# PowerSupply.net
KiCad netlist of a schematic drawn in Altium Designer
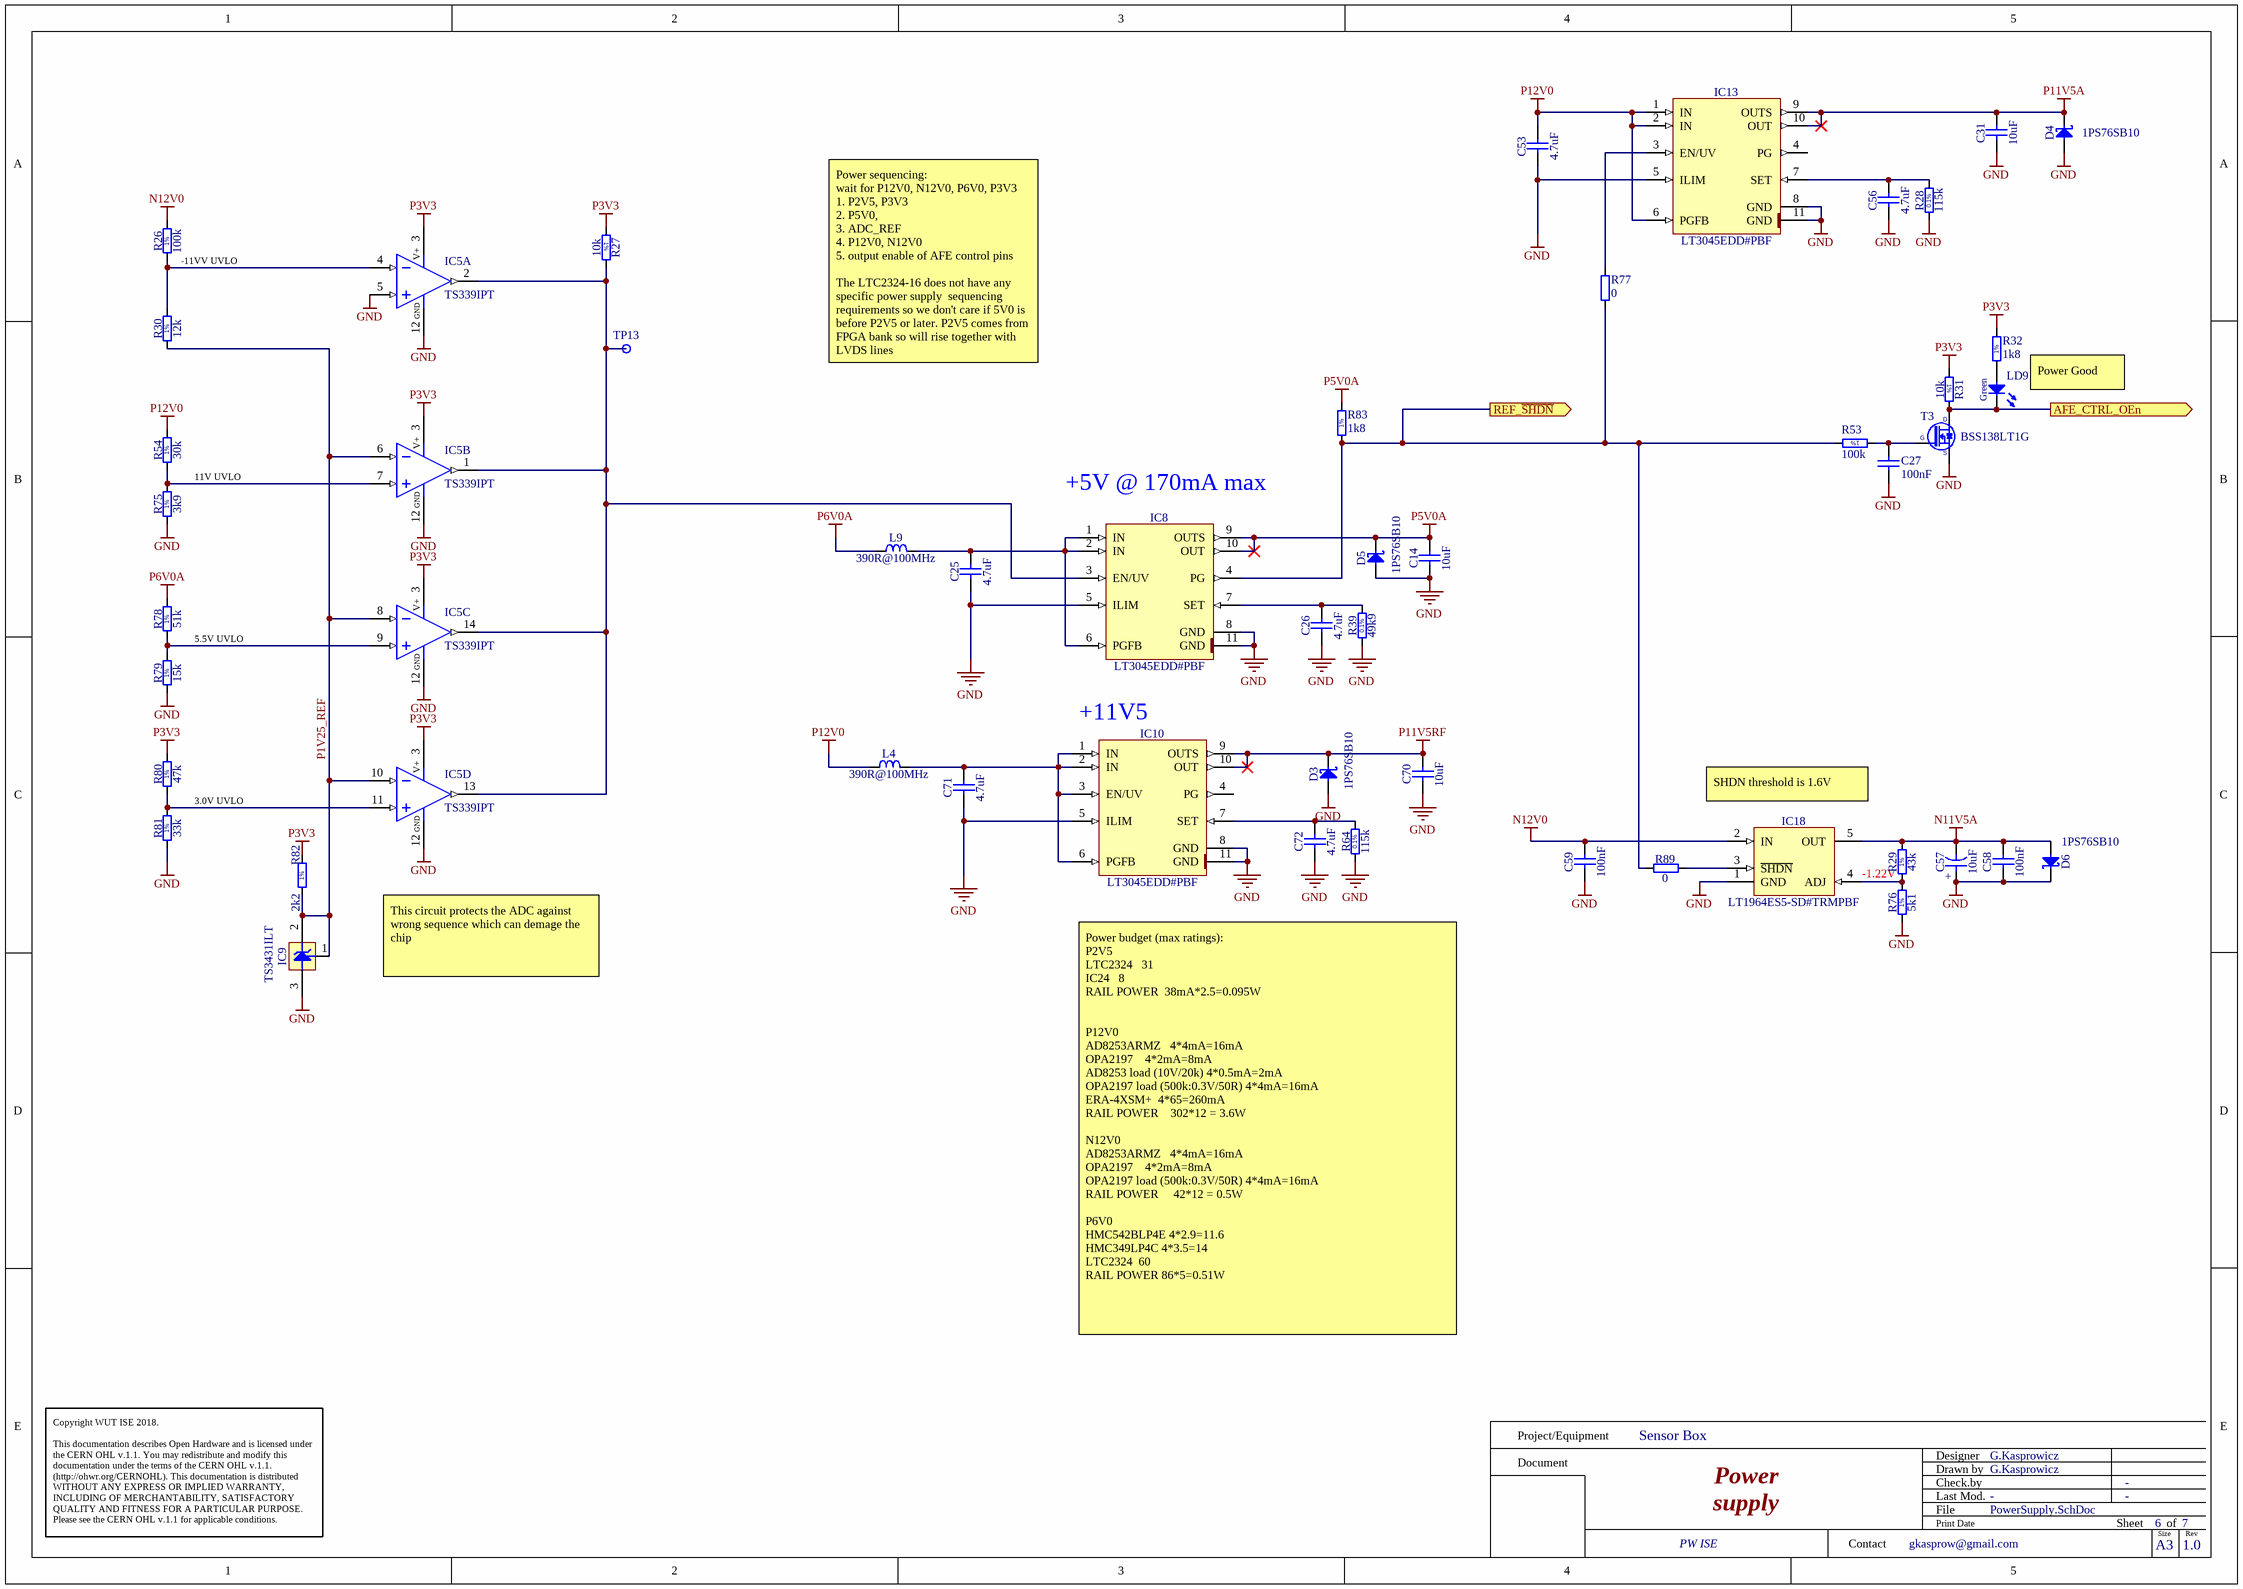
[diagram p0: PowerSupply.SchDoc]

(export (version "E")
  (design (tool "Eeschema 10.0.6"))
  (components
    (comp (ref "C14")
      (value "10uF")
      (footprint "CAPC1608X87N")
      (description "Non-polarised capacitor")
      (fields
        (field (name "PART NUMBER") "CC0603_10UF_6.3V_20%_X5R")
        (field (name "VOLTAGE") "6.3V")
        (field (name "AUTHOR") "CERN DEM JLC")
      )
      (libsource (lib "Capacitors") (part "Capacitor - non polarized"))
    )
    (comp (ref "C25")
      (value "4.7uF")
      (footprint "CAPC1709X95N")
      (description "Non-polarised capacitor")
      (fields
        (field (name "PART NUMBER") "CC0603_4.7UF_16V_10%_X5R")
        (field (name "VOLTAGE") "16V")
        (field (name "AUTHOR") "CERN DEM JLC")
      )
      (libsource (lib "Capacitors") (part "Capacitor - non polarized"))
    )
    (comp (ref "C26")
      (value "4.7uF")
      (footprint "CAPC1709X95N")
      (description "Non-polarised capacitor")
      (fields
        (field (name "PART NUMBER") "CC0603_4.7UF_16V_10%_X5R")
        (field (name "VOLTAGE") "16V")
        (field (name "AUTHOR") "CERN DEM JLC")
      )
      (libsource (lib "Capacitors") (part "Capacitor - non polarized"))
    )
    (comp (ref "C27")
      (value "100nF")
      (footprint "CAPC1005X55N")
      (description "Non-polarised capacitor")
      (fields
        (field (name "PART NUMBER") "CC0402_100NF_16V_10%_X5R")
        (field (name "VOLTAGE") "16V")
        (field (name "AUTHOR") "CERN DEM JLC")
      )
      (libsource (lib "Capacitors") (part "Capacitor - non polarized"))
    )
    (comp (ref "C31")
      (value "10uF")
      (footprint "CAPC1608X87N")
      (description "Non-polarised capacitor")
      (fields
        (field (name "PART NUMBER") "CC0603_10UF_6.3V_20%_X5R")
        (field (name "VOLTAGE") "6.3V")
        (field (name "AUTHOR") "CERN DEM JLC")
      )
      (libsource (lib "Capacitors") (part "Capacitor - non polarized"))
    )
    (comp (ref "C53")
      (value "4.7uF")
      (footprint "CAPC1709X95N")
      (description "Non-polarised capacitor")
      (fields
        (field (name "PART NUMBER") "CC0603_4.7UF_16V_10%_X5R")
        (field (name "VOLTAGE") "16V")
        (field (name "AUTHOR") "CERN DEM JLC")
      )
      (libsource (lib "Capacitors") (part "Capacitor - non polarized"))
    )
    (comp (ref "C56")
      (value "4.7uF")
      (footprint "CAPC1709X95N")
      (description "Non-polarised capacitor")
      (fields
        (field (name "PART NUMBER") "CC0603_4.7UF_16V_10%_X5R")
        (field (name "VOLTAGE") "16V")
        (field (name "AUTHOR") "CERN DEM JLC")
      )
      (libsource (lib "Capacitors") (part "Capacitor - non polarized"))
    )
    (comp (ref "C57")
      (value "10uF")
      (footprint "CAPMP3216X180N")
      (description "Polarised capacitor")
      (fields
        (field (name "PART NUMBER") "CTE3216-18_10UF_16V_20%_AVX_TCJ")
        (field (name "VOLTAGE") "16V")
        (field (name "AUTHOR") "CERN DEM JLC")
      )
      (libsource (lib "Capacitors") (part "Capacitor - polarized"))
    )
    (comp (ref "C58")
      (value "100nF")
      (footprint "CAPC1005X55N")
      (description "Non-polarised capacitor")
      (fields
        (field (name "PART NUMBER") "CC0402_100NF_16V_10%_X5R")
        (field (name "VOLTAGE") "16V")
        (field (name "AUTHOR") "CERN DEM JLC")
      )
      (libsource (lib "Capacitors") (part "Capacitor - non polarized"))
    )
    (comp (ref "C59")
      (value "100nF")
      (footprint "CAPC1005X55N")
      (description "Non-polarised capacitor")
      (fields
        (field (name "PART NUMBER") "CC0402_100NF_16V_10%_X5R")
        (field (name "VOLTAGE") "16V")
        (field (name "AUTHOR") "CERN DEM JLC")
      )
      (libsource (lib "Capacitors") (part "Capacitor - non polarized"))
    )
    (comp (ref "C70")
      (value "10uF")
      (footprint "CAPC1608X87N")
      (description "Non-polarised capacitor")
      (fields
        (field (name "PART NUMBER") "CC0603_10UF_6.3V_20%_X5R")
        (field (name "VOLTAGE") "6.3V")
        (field (name "AUTHOR") "CERN DEM JLC")
      )
      (libsource (lib "Capacitors") (part "Capacitor - non polarized"))
    )
    (comp (ref "C71")
      (value "4.7uF")
      (footprint "CAPC1709X95N")
      (description "Non-polarised capacitor")
      (fields
        (field (name "PART NUMBER") "CC0603_4.7UF_16V_10%_X5R")
        (field (name "VOLTAGE") "16V")
        (field (name "AUTHOR") "CERN DEM JLC")
      )
      (libsource (lib "Capacitors") (part "Capacitor - non polarized"))
    )
    (comp (ref "C72")
      (value "4.7uF")
      (footprint "CAPC1709X95N")
      (description "Non-polarised capacitor")
      (fields
        (field (name "PART NUMBER") "CC0603_4.7UF_16V_10%_X5R")
        (field (name "VOLTAGE") "16V")
        (field (name "AUTHOR") "CERN DEM JLC")
      )
      (libsource (lib "Capacitors") (part "Capacitor - non polarized"))
    )
    (comp (ref "D3")
      (value "1PS76SB10")
      (footprint "SOD2512X110N")
      (description "Schottky Diode")
      (fields
        (field (name "VOLTAGE") "30V")
        (field (name "POWER") "200mA")
        (field (name "AUTHOR") "CERN DEM JLC")
      )
      (libsource (lib "ICs And Semiconductors") (part "Diode Schottky"))
    )
    (comp (ref "D4")
      (value "1PS76SB10")
      (footprint "SOD2512X110N")
      (description "Schottky Diode")
      (fields
        (field (name "VOLTAGE") "30V")
        (field (name "POWER") "200mA")
        (field (name "AUTHOR") "CERN DEM JLC")
      )
      (libsource (lib "ICs And Semiconductors") (part "Diode Schottky"))
    )
    (comp (ref "D5")
      (value "1PS76SB10")
      (footprint "SOD2512X110N")
      (description "Schottky Diode")
      (fields
        (field (name "VOLTAGE") "30V")
        (field (name "POWER") "200mA")
        (field (name "AUTHOR") "CERN DEM JLC")
      )
      (libsource (lib "ICs And Semiconductors") (part "Diode Schottky"))
    )
    (comp (ref "D6")
      (value "1PS76SB10")
      (footprint "SOD2512X110N")
      (description "Schottky Diode")
      (fields
        (field (name "VOLTAGE") "30V")
        (field (name "POWER") "200mA")
        (field (name "AUTHOR") "CERN DEM JLC")
      )
      (libsource (lib "ICs And Semiconductors") (part "Diode Schottky"))
    )
    (comp (ref "IC5")
      (value "TS339IPT")
      (footprint "SOP65P640X120-14N")
      (description "Quad comparator")
      (fields (field (name "MANUFACTURER") "ST") (field (name "AUTHOR") "GK"))
      (libsource (lib "LIBRARY_SCH") (part "CMP_TS339"))
    )
    (comp (ref "IC8")
      (value "LT3045EDD#PBF")
      (footprint "SON50P300X300X80-11N-R175X248")
      (description "20V, 500mA, Ultralow Noise, Ultrahigh PSRR Linear Regulator")
      (fields (field (name "MANUFACTURER") "LINEAR TECHNOLOGY") (field (name "AUTHOR") "CERN DEM JLC"))
      (libsource (lib "ICs And Semiconductors") (part "LT3045EDD"))
    )
    (comp (ref "IC9")
      (value "TS3431ILT")
      (footprint "SOT95P237X112-3N")
      (description "Precision Reference 1=Adj 2=Cathode 3=Anode")
      (fields (field (name "MANUFACTURER") "ST MICROELECTRONICS") (field (name "AUTHOR") "CERN DEM JLC"))
      (libsource (lib "ICs And Semiconductors") (part "VREF 1ADJ-2C-3A"))
    )
    (comp (ref "IC10")
      (value "LT3045EDD#PBF")
      (footprint "SON50P300X300X80-11N-R175X248")
      (description "20V, 500mA, Ultralow Noise, Ultrahigh PSRR Linear Regulator")
      (fields (field (name "MANUFACTURER") "LINEAR TECHNOLOGY") (field (name "AUTHOR") "CERN DEM JLC"))
      (libsource (lib "ICs And Semiconductors") (part "LT3045EDD"))
    )
    (comp (ref "IC13")
      (value "LT3045EDD#PBF")
      (footprint "SON50P300X300X80-11N-R175X248")
      (description "20V, 500mA, Ultralow Noise, Ultrahigh PSRR Linear Regulator")
      (fields (field (name "MANUFACTURER") "LINEAR TECHNOLOGY") (field (name "AUTHOR") "CERN DEM JLC"))
      (libsource (lib "ICs And Semiconductors") (part "LT3045EDD"))
    )
    (comp (ref "IC18")
      (value "LT1964ES5-SD#TRMPBF")
      (footprint "SOT95P280X100-5N")
      (description "200mA, Low Noise, Low Dropout Negative Micropower Regulator")
      (fields (field (name "MANUFACTURER") "LINEAR TECHNOLOGY") (field (name "AUTHOR") "CERN DEM JLC"))
      (libsource (lib "ICs And Semiconductors") (part "LT1964-SD"))
    )
    (comp (ref "L4")
      (value "390R@100MHz")
      (footprint "INDC1608X95N")
      (description "Inductor")
      (fields
        (field (name "PART NUMBER") "IND0603_TDK_MPZ1608R391A")
        (field (name "POWER") "1.2A")
        (field (name "AUTHOR") "CERN DEM JLC")
      )
      (libsource (lib "Inductors & Transformers") (part "Inductor"))
    )
    (comp (ref "L9")
      (value "390R@100MHz")
      (footprint "INDC1608X95N")
      (description "Inductor")
      (fields
        (field (name "PART NUMBER") "IND0603_TDK_MPZ1608R391A")
        (field (name "POWER") "1.2A")
        (field (name "AUTHOR") "CERN DEM JLC")
      )
      (libsource (lib "Inductors & Transformers") (part "Inductor"))
    )
    (comp (ref "LD9")
      (value "Green")
      (footprint "LED_KINGBRIGHT_KPH-1608CGCK")
      (description "LED Green 1C 2A")
      (fields
        (field (name "PART NUMBER") "LED_KINGBRIGHT_KPH-1608CGCK")
        (field (name "MANUFACTURER") "KINGBRIGHT")
        (field (name "AUTHOR") "CERN DEM JLC")
      )
      (libsource (lib "ICs And Semiconductors") (part "LED Green 1C 2A"))
    )
    (comp (ref "R26")
      (value "100k")
      (footprint "RESC1005X40N")
      (description "Resistor - 1%")
      (fields
        (field (name "PART NUMBER") "R0402_100K_1%_0.0625W_100PPM")
        (field (name "POWER") "0.0625W")
        (field (name "AUTHOR") "CERN DEM JLC")
      )
      (libsource (lib "Resistors") (part "Resistor - 1%"))
    )
    (comp (ref "R27")
      (value "10k")
      (footprint "RESC1005X40N")
      (description "Resistor - 1%")
      (fields
        (field (name "PART NUMBER") "R0402_10K_1%_0.0625W_100PPM")
        (field (name "POWER") "0.0625W")
        (field (name "AUTHOR") "CERN DEM JLC")
      )
      (libsource (lib "Resistors") (part "Resistor - 1%"))
    )
    (comp (ref "R28")
      (value "115k")
      (footprint "RESC1608X55N")
      (description "Resistor - 0.1%")
      (fields
        (field (name "PART NUMBER") "R0603_115K_0.1%_0.063W_10PPM")
        (field (name "POWER") "0.063W")
        (field (name "AUTHOR") "CERN DEM JLC")
      )
      (libsource (lib "Resistors") (part "Resistor - 0.1%"))
    )
    (comp (ref "R29")
      (value "43k")
      (footprint "RESC1005X40N")
      (description "Resistor - 1%")
      (fields
        (field (name "PART NUMBER") "R0402_43K_1%_0.0625W_100PPM")
        (field (name "POWER") "0.0625W")
        (field (name "AUTHOR") "CERN DEM JLC")
      )
      (libsource (lib "Resistors") (part "Resistor - 1%"))
    )
    (comp (ref "R30")
      (value "12k")
      (footprint "RESC1005X40N")
      (description "Resistor - 1%")
      (fields
        (field (name "PART NUMBER") "R0402_12K_1%_0.0625W_100PPM")
        (field (name "POWER") "0.0625W")
        (field (name "AUTHOR") "CERN DEM JLC")
      )
      (libsource (lib "Resistors") (part "Resistor - 1%"))
    )
    (comp (ref "R31")
      (value "10k")
      (footprint "RESC1005X40N")
      (description "Resistor - 1%")
      (fields
        (field (name "PART NUMBER") "R0402_10K_1%_0.0625W_100PPM")
        (field (name "POWER") "0.0625W")
        (field (name "AUTHOR") "CERN DEM JLC")
      )
      (libsource (lib "Resistors") (part "Resistor - 1%"))
    )
    (comp (ref "R32")
      (value "1k8")
      (footprint "RESC1608X55N")
      (description "Resistor - 1%")
      (fields
        (field (name "PART NUMBER") "R0603_1K8_1%_0.1W_100PPM")
        (field (name "POWER") "0.1W")
        (field (name "AUTHOR") "CERN DEM JLC")
      )
      (libsource (lib "Resistors") (part "Resistor - 1%"))
    )
    (comp (ref "R39")
      (value "49k9")
      (footprint "RESC1608X55N")
      (description "Resistor - 0.1%")
      (fields
        (field (name "PART NUMBER") "R0603_49K9_0.1%_0.063W_10PPM")
        (field (name "POWER") "0.063W")
        (field (name "AUTHOR") "CERN DEM JLC")
      )
      (libsource (lib "Resistors") (part "Resistor - 0.1%"))
    )
    (comp (ref "R53")
      (value "100k")
      (footprint "RESC1608X55N")
      (description "Resistor - 1%")
      (fields
        (field (name "PART NUMBER") "R0603_100K_1%_0.1W_100PPM")
        (field (name "POWER") "0.1W")
        (field (name "AUTHOR") "CERN DEM JLC")
      )
      (libsource (lib "Resistors") (part "Resistor - 1%"))
    )
    (comp (ref "R54")
      (value "30k")
      (footprint "RESC1005X40N")
      (description "Resistor - 1%")
      (fields
        (field (name "PART NUMBER") "R0402_30K_1%_0.0625W_100PPM")
        (field (name "POWER") "0.0625W")
        (field (name "AUTHOR") "CERN DEM JLC")
      )
      (libsource (lib "Resistors") (part "Resistor - 1%"))
    )
    (comp (ref "R64")
      (value "115k")
      (footprint "RESC1608X55N")
      (description "Resistor - 0.1%")
      (fields
        (field (name "PART NUMBER") "R0603_115K_0.1%_0.063W_10PPM")
        (field (name "POWER") "0.063W")
        (field (name "AUTHOR") "CERN DEM JLC")
      )
      (libsource (lib "Resistors") (part "Resistor - 0.1%"))
    )
    (comp (ref "R75")
      (value "3k9")
      (footprint "RESC1005X40N")
      (description "Resistor - 1%")
      (fields
        (field (name "PART NUMBER") "R0402_3K9_1%_0.0625W_100PPM")
        (field (name "POWER") "0.0625W")
        (field (name "AUTHOR") "CERN DEM JLC")
      )
      (libsource (lib "Resistors") (part "Resistor - 1%"))
    )
    (comp (ref "R76")
      (value "5k1")
      (footprint "RESC1005X40N")
      (description "Resistor - 1%")
      (fields
        (field (name "PART NUMBER") "R0402_5K1_1%_0.0625W_100PPM")
        (field (name "POWER") "0.0625W")
        (field (name "AUTHOR") "CERN DEM JLC")
      )
      (libsource (lib "Resistors") (part "Resistor - 1%"))
    )
    (comp (ref "R77")
      (value "0")
      (footprint "RESC1005X40N")
      (description "Resistor")
      (fields
        (field (name "PART NUMBER") "R0402_0R_JUMPER")
        (field (name "MANUFACTURER") "GENERIC")
        (field (name "AUTHOR") "CERN DEM JLC")
      )
      (libsource (lib "Resistors") (part "Resistor"))
    )
    (comp (ref "R78")
      (value "51k")
      (footprint "RESC1005X40N")
      (description "Resistor - 1%")
      (fields
        (field (name "PART NUMBER") "R0402_51K_1%_0.0625W_100PPM")
        (field (name "POWER") "0.0625W")
        (field (name "AUTHOR") "CERN DEM JLC")
      )
      (libsource (lib "Resistors") (part "Resistor - 1%"))
    )
    (comp (ref "R79")
      (value "15k")
      (footprint "RESC1005X40N")
      (description "Resistor - 1%")
      (fields
        (field (name "PART NUMBER") "R0402_15K_1%_0.0625W_100PPM")
        (field (name "POWER") "0.0625W")
        (field (name "AUTHOR") "CERN DEM JMW")
      )
      (libsource (lib "Resistors") (part "Resistor - 1%"))
    )
    (comp (ref "R80")
      (value "47k")
      (footprint "RESC1005X40N")
      (description "Resistor - 1%")
      (fields
        (field (name "PART NUMBER") "R0402_47K_1%_0.0625W_100PPM")
        (field (name "POWER") "0.0625W")
        (field (name "AUTHOR") "CERN DEM JLC")
      )
      (libsource (lib "Resistors") (part "Resistor - 1%"))
    )
    (comp (ref "R81")
      (value "33k")
      (footprint "RESC1005X40N")
      (description "Resistor - 1%")
      (fields
        (field (name "PART NUMBER") "R0402_33K_1%_0.0625W_100PPM")
        (field (name "POWER") "0.0625W")
        (field (name "AUTHOR") "CERN DEM JLC")
      )
      (libsource (lib "Resistors") (part "Resistor - 1%"))
    )
    (comp (ref "R82")
      (value "2k2")
      (footprint "RESC1005X40N")
      (description "Resistor - 1%")
      (fields
        (field (name "PART NUMBER") "R0402_2K2_1%_0.0625W_100PPM")
        (field (name "POWER") "0.0625W")
        (field (name "AUTHOR") "CERN DEM JLC")
      )
      (libsource (lib "Resistors") (part "Resistor - 1%"))
    )
    (comp (ref "R83")
      (value "1k8")
      (footprint "RESC1608X55N")
      (description "Resistor - 1%")
      (fields
        (field (name "PART NUMBER") "R0603_1K8_1%_0.1W_100PPM")
        (field (name "POWER") "0.1W")
        (field (name "AUTHOR") "CERN DEM JLC")
      )
      (libsource (lib "Resistors") (part "Resistor - 1%"))
    )
    (comp (ref "R89")
      (value "0")
      (footprint "RESC1005X40N")
      (description "Resistor")
      (fields
        (field (name "PART NUMBER") "R0402_0R_JUMPER")
        (field (name "MANUFACTURER") "GENERIC")
        (field (name "AUTHOR") "CERN DEM JLC")
      )
      (libsource (lib "Resistors") (part "Resistor"))
    )
    (comp (ref "T3")
      (value "BSS138LT1G")
      (footprint "SOT95P240X110-3N")
      (description "N-CHANNEL MOSFET WITH DIODE")
      (fields (field (name "MANUFACTURER") "ON SEMICONDUCTOR") (field (name "AUTHOR") "CERN DEM JLC"))
      (libsource (lib "ICs And Semiconductors") (part "N-MOSFET-D 1G 2S 3D"))
    )
    (comp (ref "TP13")
      (value "Test Point")
      (footprint "TPS127")
      (fields (field (name "PART NUMBER") "SMD_PAD_1.27X1.27MM") (field (name "AUTHOR") "CERN DEM JLC"))
      (libsource (lib "Eletro-mechanical") (part "Test Point"))
    )
  )
  (nets
    (net (code "1") (name "/AFE_CTRL_OEn") (class "Default")
      (node (ref "LD9") (pin "1") (pinfunction "C_1") (pintype "passive"))
      (node (ref "R31") (pin "2") (pinfunction "2_2") (pintype "passive"))
      (node (ref "T3") (pin "3") (pinfunction "D_3") (pintype "passive"))
    )
    (net (code "2") (name "/P1V25_REF") (class "Default")
      (node (ref "IC5") (pin "10") (pinfunction "IN-_10") (pintype "input"))
      (node (ref "IC5") (pin "6") (pinfunction "IN-_6") (pintype "input"))
      (node (ref "IC5") (pin "8") (pinfunction "IN-_8") (pintype "input"))
      (node (ref "IC9") (pin "1") (pinfunction "Adj_1") (pintype "passive"))
      (node (ref "IC9") (pin "2") (pinfunction "C_2") (pintype "passive"))
      (node (ref "R30") (pin "1") (pinfunction "1_1") (pintype "passive"))
      (node (ref "R82") (pin "1") (pinfunction "1_1") (pintype "passive"))
    )
    (net (code "3") (name "/REF_~{SHDN}") (class "Default")
      (node (ref "IC8") (pin "4") (pinfunction "PG_4") (pintype "output"))
      (node (ref "R53") (pin "2") (pinfunction "2_2") (pintype "passive"))
      (node (ref "R77") (pin "1") (pinfunction "1_1") (pintype "passive"))
      (node (ref "R83") (pin "1") (pinfunction "1_1") (pintype "passive"))
      (node (ref "R89") (pin "1") (pinfunction "1_1") (pintype "passive"))
    )
    (net (code "4") (name "GND") (class "Default")
      (node (ref "C14") (pin "1") (pinfunction "1_1") (pintype "passive"))
      (node (ref "C25") (pin "1") (pinfunction "1_1") (pintype "passive"))
      (node (ref "C26") (pin "1") (pinfunction "1_1") (pintype "passive"))
      (node (ref "C27") (pin "2") (pinfunction "2_2") (pintype "passive"))
      (node (ref "C31") (pin "1") (pinfunction "1_1") (pintype "passive"))
      (node (ref "C53") (pin "1") (pinfunction "1_1") (pintype "passive"))
      (node (ref "C56") (pin "1") (pinfunction "1_1") (pintype "passive"))
      (node (ref "C57") (pin "1") (pinfunction "1_1") (pintype "passive"))
      (node (ref "C58") (pin "1") (pinfunction "1_1") (pintype "passive"))
      (node (ref "C59") (pin "1") (pinfunction "1_1") (pintype "passive"))
      (node (ref "C70") (pin "1") (pinfunction "1_1") (pintype "passive"))
      (node (ref "C71") (pin "1") (pinfunction "1_1") (pintype "passive"))
      (node (ref "C72") (pin "1") (pinfunction "1_1") (pintype "passive"))
      (node (ref "D3") (pin "2") (pinfunction "A_2") (pintype "passive"))
      (node (ref "D4") (pin "2") (pinfunction "A_2") (pintype "passive"))
      (node (ref "D5") (pin "2") (pinfunction "A_2") (pintype "passive"))
      (node (ref "D6") (pin "1") (pinfunction "C_1") (pintype "passive"))
      (node (ref "IC10") (pin "11") (pinfunction "GND_11") (pintype "power_in"))
      (node (ref "IC10") (pin "5") (pinfunction "ILIM_5") (pintype "input"))
      (node (ref "IC10") (pin "8") (pinfunction "GND_8") (pintype "power_in"))
      (node (ref "IC13") (pin "11") (pinfunction "GND_11") (pintype "power_in"))
      (node (ref "IC13") (pin "5") (pinfunction "ILIM_5") (pintype "input"))
      (node (ref "IC13") (pin "8") (pinfunction "GND_8") (pintype "power_in"))
      (node (ref "IC18") (pin "1") (pinfunction "GND_1") (pintype "power_in"))
      (node (ref "IC5") (pin "12") (pinfunction "GND_12") (pintype "power_in"))
      (node (ref "IC5") (pin "5") (pinfunction "IN+_5") (pintype "input"))
      (node (ref "IC8") (pin "11") (pinfunction "GND_11") (pintype "power_in"))
      (node (ref "IC8") (pin "5") (pinfunction "ILIM_5") (pintype "input"))
      (node (ref "IC8") (pin "8") (pinfunction "GND_8") (pintype "power_in"))
      (node (ref "IC9") (pin "3") (pinfunction "A_3") (pintype "passive"))
      (node (ref "R28") (pin "1") (pinfunction "1_1") (pintype "passive"))
      (node (ref "R39") (pin "1") (pinfunction "1_1") (pintype "passive"))
      (node (ref "R64") (pin "1") (pinfunction "1_1") (pintype "passive"))
      (node (ref "R75") (pin "1") (pinfunction "1_1") (pintype "passive"))
      (node (ref "R76") (pin "1") (pinfunction "1_1") (pintype "passive"))
      (node (ref "R79") (pin "1") (pinfunction "1_1") (pintype "passive"))
      (node (ref "R81") (pin "1") (pinfunction "1_1") (pintype "passive"))
      (node (ref "T3") (pin "2") (pinfunction "S_2") (pintype "passive"))
    )
    (net (code "5") (name "N11V5A") (class "Default")
      (node (ref "C57") (pin "2") (pinfunction "2_2") (pintype "passive"))
      (node (ref "C58") (pin "2") (pinfunction "2_2") (pintype "passive"))
      (node (ref "D6") (pin "2") (pinfunction "A_2") (pintype "passive"))
      (node (ref "IC18") (pin "5") (pinfunction "OUT_5") (pintype "power_in"))
      (node (ref "R29") (pin "2") (pinfunction "2_2") (pintype "passive"))
    )
    (net (code "6") (name "N12V0") (class "Default")
      (node (ref "C59") (pin "2") (pinfunction "2_2") (pintype "passive"))
      (node (ref "IC18") (pin "2") (pinfunction "IN_2") (pintype "input"))
      (node (ref "R26") (pin "2") (pinfunction "2_2") (pintype "passive"))
    )
    (net (code "7") (name "Net-(IC5A-IN-)") (class "Default")
      (node (ref "IC5") (pin "4") (pinfunction "IN-_4") (pintype "input"))
      (node (ref "R26") (pin "1") (pinfunction "1_1") (pintype "passive"))
      (node (ref "R30") (pin "2") (pinfunction "2_2") (pintype "passive"))
    )
    (net (code "8") (name "Net-(IC5A-OUT)") (class "Default")
      (node (ref "IC5") (pin "1") (pinfunction "OUT_1") (pintype "output"))
      (node (ref "IC5") (pin "13") (pinfunction "OUT_13") (pintype "output"))
      (node (ref "IC5") (pin "14") (pinfunction "OUT_14") (pintype "output"))
      (node (ref "IC5") (pin "2") (pinfunction "OUT_2") (pintype "output"))
      (node (ref "IC8") (pin "3") (pinfunction "EN/UV_3") (pintype "input"))
      (node (ref "R27") (pin "2") (pinfunction "2_2") (pintype "passive"))
      (node (ref "TP13") (pin "1") (pinfunction "1_1") (pintype "bidirectional"))
    )
    (net (code "9") (name "Net-(IC5B-IN+)") (class "Default")
      (node (ref "IC5") (pin "7") (pinfunction "IN+_7") (pintype "input"))
      (node (ref "R54") (pin "1") (pinfunction "1_1") (pintype "passive"))
      (node (ref "R75") (pin "2") (pinfunction "2_2") (pintype "passive"))
    )
    (net (code "10") (name "Net-(IC5C-IN+)") (class "Default")
      (node (ref "IC5") (pin "9") (pinfunction "IN+_9") (pintype "input"))
      (node (ref "R78") (pin "1") (pinfunction "1_1") (pintype "passive"))
      (node (ref "R79") (pin "2") (pinfunction "2_2") (pintype "passive"))
    )
    (net (code "11") (name "Net-(IC5D-IN+)") (class "Default")
      (node (ref "IC5") (pin "11") (pinfunction "IN+_11") (pintype "input"))
      (node (ref "R80") (pin "1") (pinfunction "1_1") (pintype "passive"))
      (node (ref "R81") (pin "2") (pinfunction "2_2") (pintype "passive"))
    )
    (net (code "12") (name "Net-(IC8-PGFB)") (class "Default")
      (node (ref "C25") (pin "2") (pinfunction "2_2") (pintype "passive"))
      (node (ref "IC8") (pin "1") (pinfunction "IN_1") (pintype "input"))
      (node (ref "IC8") (pin "2") (pinfunction "IN_2") (pintype "input"))
      (node (ref "IC8") (pin "6") (pinfunction "PGFB_6") (pintype "input"))
      (node (ref "L9") (pin "2") (pinfunction "2_2") (pintype "passive"))
    )
    (net (code "13") (name "Net-(IC8-SET)") (class "Default")
      (node (ref "C26") (pin "2") (pinfunction "2_2") (pintype "passive"))
      (node (ref "IC8") (pin "7") (pinfunction "SET_7") (pintype "input"))
      (node (ref "R39") (pin "2") (pinfunction "2_2") (pintype "passive"))
    )
    (net (code "14") (name "Net-(IC10-EN{slash}UV)") (class "Default")
      (node (ref "C71") (pin "2") (pinfunction "2_2") (pintype "passive"))
      (node (ref "IC10") (pin "1") (pinfunction "IN_1") (pintype "input"))
      (node (ref "IC10") (pin "2") (pinfunction "IN_2") (pintype "input"))
      (node (ref "IC10") (pin "3") (pinfunction "EN/UV_3") (pintype "input"))
      (node (ref "IC10") (pin "6") (pinfunction "PGFB_6") (pintype "input"))
      (node (ref "L4") (pin "2") (pinfunction "2_2") (pintype "passive"))
    )
    (net (code "15") (name "Net-(IC10-SET)") (class "Default")
      (node (ref "C72") (pin "2") (pinfunction "2_2") (pintype "passive"))
      (node (ref "IC10") (pin "7") (pinfunction "SET_7") (pintype "input"))
      (node (ref "R64") (pin "2") (pinfunction "2_2") (pintype "passive"))
    )
    (net (code "16") (name "Net-(IC13-EN{slash}UV)") (class "Default")
      (node (ref "IC13") (pin "3") (pinfunction "EN/UV_3") (pintype "input"))
      (node (ref "R77") (pin "2") (pinfunction "2_2") (pintype "passive"))
    )
    (net (code "17") (name "Net-(IC13-SET)") (class "Default")
      (node (ref "C56") (pin "2") (pinfunction "2_2") (pintype "passive"))
      (node (ref "IC13") (pin "7") (pinfunction "SET_7") (pintype "input"))
      (node (ref "R28") (pin "2") (pinfunction "2_2") (pintype "passive"))
    )
    (net (code "18") (name "Net-(IC18-ADJ)") (class "Default")
      (node (ref "IC18") (pin "4") (pinfunction "ADJ_4") (pintype "input"))
      (node (ref "R29") (pin "1") (pinfunction "1_1") (pintype "passive"))
      (node (ref "R76") (pin "2") (pinfunction "2_2") (pintype "passive"))
    )
    (net (code "19") (name "Net-(IC18-~{SHDN})") (class "Default")
      (node (ref "IC18") (pin "3") (pinfunction "~{SHDN}_3") (pintype "input"))
      (node (ref "R89") (pin "2") (pinfunction "2_2") (pintype "passive"))
    )
    (net (code "20") (name "Net-(LD9-A)") (class "Default")
      (node (ref "LD9") (pin "2") (pinfunction "A_2") (pintype "passive"))
      (node (ref "R32") (pin "1") (pinfunction "1_1") (pintype "passive"))
    )
    (net (code "21") (name "Net-(T3-G)") (class "Default")
      (node (ref "C27") (pin "1") (pinfunction "1_1") (pintype "passive"))
      (node (ref "R53") (pin "1") (pinfunction "1_1") (pintype "passive"))
      (node (ref "T3") (pin "1") (pinfunction "G_1") (pintype "passive"))
    )
    (net (code "22") (name "P3V3") (class "Default")
      (node (ref "IC5") (pin "3") (pinfunction "V+_3") (pintype "power_in"))
      (node (ref "R27") (pin "1") (pinfunction "1_1") (pintype "passive"))
      (node (ref "R31") (pin "1") (pinfunction "1_1") (pintype "passive"))
      (node (ref "R32") (pin "2") (pinfunction "2_2") (pintype "passive"))
      (node (ref "R80") (pin "2") (pinfunction "2_2") (pintype "passive"))
      (node (ref "R82") (pin "2") (pinfunction "2_2") (pintype "passive"))
    )
    (net (code "23") (name "P5V0A") (class "Default")
      (node (ref "C14") (pin "2") (pinfunction "2_2") (pintype "passive"))
      (node (ref "D5") (pin "1") (pinfunction "C_1") (pintype "passive"))
      (node (ref "IC8") (pin "10") (pinfunction "OUT_10") (pintype "output"))
      (node (ref "IC8") (pin "9") (pinfunction "OUTS_9") (pintype "output"))
      (node (ref "R83") (pin "2") (pinfunction "2_2") (pintype "passive"))
    )
    (net (code "24") (name "P6V0A") (class "Default")
      (node (ref "L9") (pin "1") (pinfunction "1_1") (pintype "passive"))
      (node (ref "R78") (pin "2") (pinfunction "2_2") (pintype "passive"))
    )
    (net (code "25") (name "P11V5A") (class "Default")
      (node (ref "C31") (pin "2") (pinfunction "2_2") (pintype "passive"))
      (node (ref "D4") (pin "1") (pinfunction "C_1") (pintype "passive"))
      (node (ref "IC13") (pin "10") (pinfunction "OUT_10") (pintype "output"))
      (node (ref "IC13") (pin "9") (pinfunction "OUTS_9") (pintype "output"))
    )
    (net (code "26") (name "P11V5RF") (class "Default")
      (node (ref "C70") (pin "2") (pinfunction "2_2") (pintype "passive"))
      (node (ref "D3") (pin "1") (pinfunction "C_1") (pintype "passive"))
      (node (ref "IC10") (pin "10") (pinfunction "OUT_10") (pintype "output"))
      (node (ref "IC10") (pin "9") (pinfunction "OUTS_9") (pintype "output"))
    )
    (net (code "27") (name "P12V0") (class "Default")
      (node (ref "C53") (pin "2") (pinfunction "2_2") (pintype "passive"))
      (node (ref "IC13") (pin "1") (pinfunction "IN_1") (pintype "input"))
      (node (ref "IC13") (pin "2") (pinfunction "IN_2") (pintype "input"))
      (node (ref "IC13") (pin "6") (pinfunction "PGFB_6") (pintype "input"))
      (node (ref "L4") (pin "1") (pinfunction "1_1") (pintype "passive"))
      (node (ref "R54") (pin "2") (pinfunction "2_2") (pintype "passive"))
    )
    (net (code "28") (name "unconnected-(IC10-PG-Pad4)") (class "Default")
      (node (ref "IC10") (pin "4") (pinfunction "PG_4") (pintype "output"))
    )
    (net (code "29") (name "unconnected-(IC13-PG-Pad4)") (class "Default")
      (node (ref "IC13") (pin "4") (pinfunction "PG_4") (pintype "output"))
    )
  )
)
